# BottomBoard.net
KiCad netlist of a schematic drawn in Altium Designer
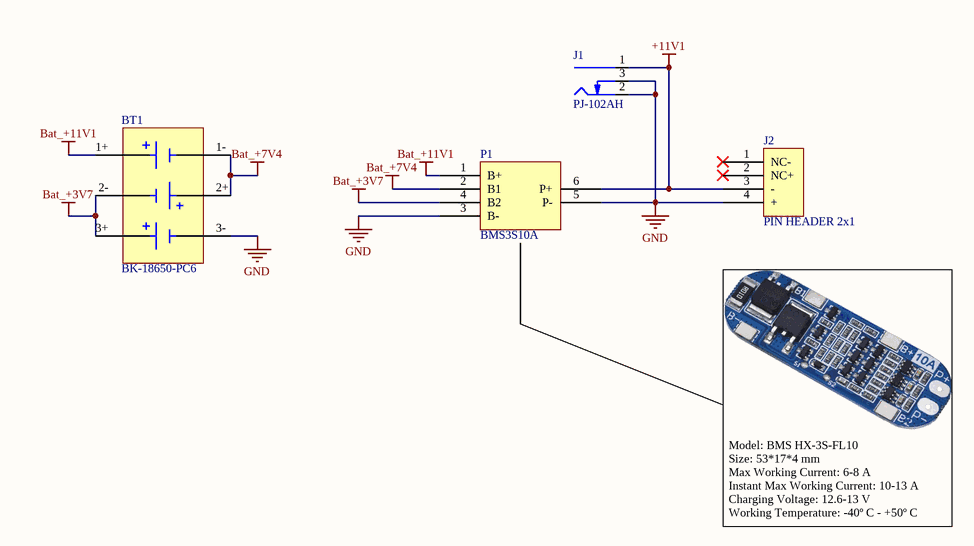
[diagram p0: BottomBoard.SchDoc]

(export (version "E")
  (design (tool "Eeschema 10.0.6"))
  (components
    (comp (ref "BT1")
      (value "BK-18650-PC6")
      (footprint "BottomBoardLib:BAT_BK-18650-PC6")
      (description "Battery Holder _Open_ 18650 3 Cell PC Pin")
      (fields (field (name "MF") "MPD"))
      (libsource (lib "BottomBoardLib") (part "BK-18650-PC6"))
    )
    (comp (ref "J1")
      (value "PJ-102AH")
      (footprint "CUI PJ-102AH")
      (description "CONN PWR JACK 2X5.5MM SOLDER")
      (fields (field (name "MANUFACTURER") "CUI Devices"))
      (libsource (lib "BottomBoardLib") (part "PJ-102AH"))
    )
    (comp (ref "J2")
      (value "PIN HEADER 2x1")
      (footprint "TopBoardLib:M20-9950245")
      (description "M20-9950245 Pin Connector")
      (libsource (lib "TopBoardLib") (part "M20-9950245"))
    )
    (comp (ref "P1") (value "BMS3S10A") (footprint "BMS") (libsource (lib "Robot") (part "BMS")))
  )
  (nets
    (net (code "1") (name "+11V1") (class "Default")
      (node (ref "J1") (pin "1") (pinfunction "Centre_1") (pintype "passive"))
      (node (ref "J2") (pin "3") (pinfunction "-_3") (pintype "power_in"))
      (node (ref "P1") (pin "6") (pinfunction "P+_6") (pintype "passive"))
    )
    (net (code "2") (name "Bat_+3V7") (class "Default")
      (node (ref "BT1") (pin "2-") (pinfunction "2-_2-") (pintype "passive"))
      (node (ref "BT1") (pin "3+") (pinfunction "3+_3+") (pintype "passive"))
      (node (ref "P1") (pin "4") (pinfunction "B2_4") (pintype "passive"))
    )
    (net (code "3") (name "Bat_+7V4") (class "Default")
      (node (ref "BT1") (pin "1-") (pinfunction "1-_1-") (pintype "passive"))
      (node (ref "BT1") (pin "2+") (pinfunction "2+_2+") (pintype "passive"))
      (node (ref "P1") (pin "2") (pinfunction "B1_2") (pintype "passive"))
    )
    (net (code "4") (name "Bat_+11V1") (class "Default")
      (node (ref "BT1") (pin "1+") (pinfunction "1+_1+") (pintype "passive"))
      (node (ref "P1") (pin "1") (pinfunction "B+_1") (pintype "passive"))
    )
    (net (code "5") (name "GND") (class "Default")
      (node (ref "BT1") (pin "3-") (pinfunction "3-_3-") (pintype "passive"))
      (node (ref "J1") (pin "2") (pinfunction "Outer_2") (pintype "passive"))
      (node (ref "J1") (pin "3") (pinfunction "SW_3") (pintype "passive"))
      (node (ref "J2") (pin "4") (pinfunction "+_4") (pintype "power_in"))
      (node (ref "P1") (pin "3") (pinfunction "B-_3") (pintype "passive"))
      (node (ref "P1") (pin "5") (pinfunction "P-_5") (pintype "passive"))
    )
    (net (code "6") (name "unconnected-(J2-NC+-Pad2)") (class "Default")
      (node (ref "J2") (pin "2") (pinfunction "NC+_2") (pintype "power_in+no_connect"))
    )
    (net (code "7") (name "unconnected-(J2-NC--Pad1)") (class "Default")
      (node (ref "J2") (pin "1") (pinfunction "NC-_1") (pintype "power_in+no_connect"))
    )
  )
)
